# Raincenter_RS232_Converter.net
KiCad netlist of a schematic drawn in EAGLE
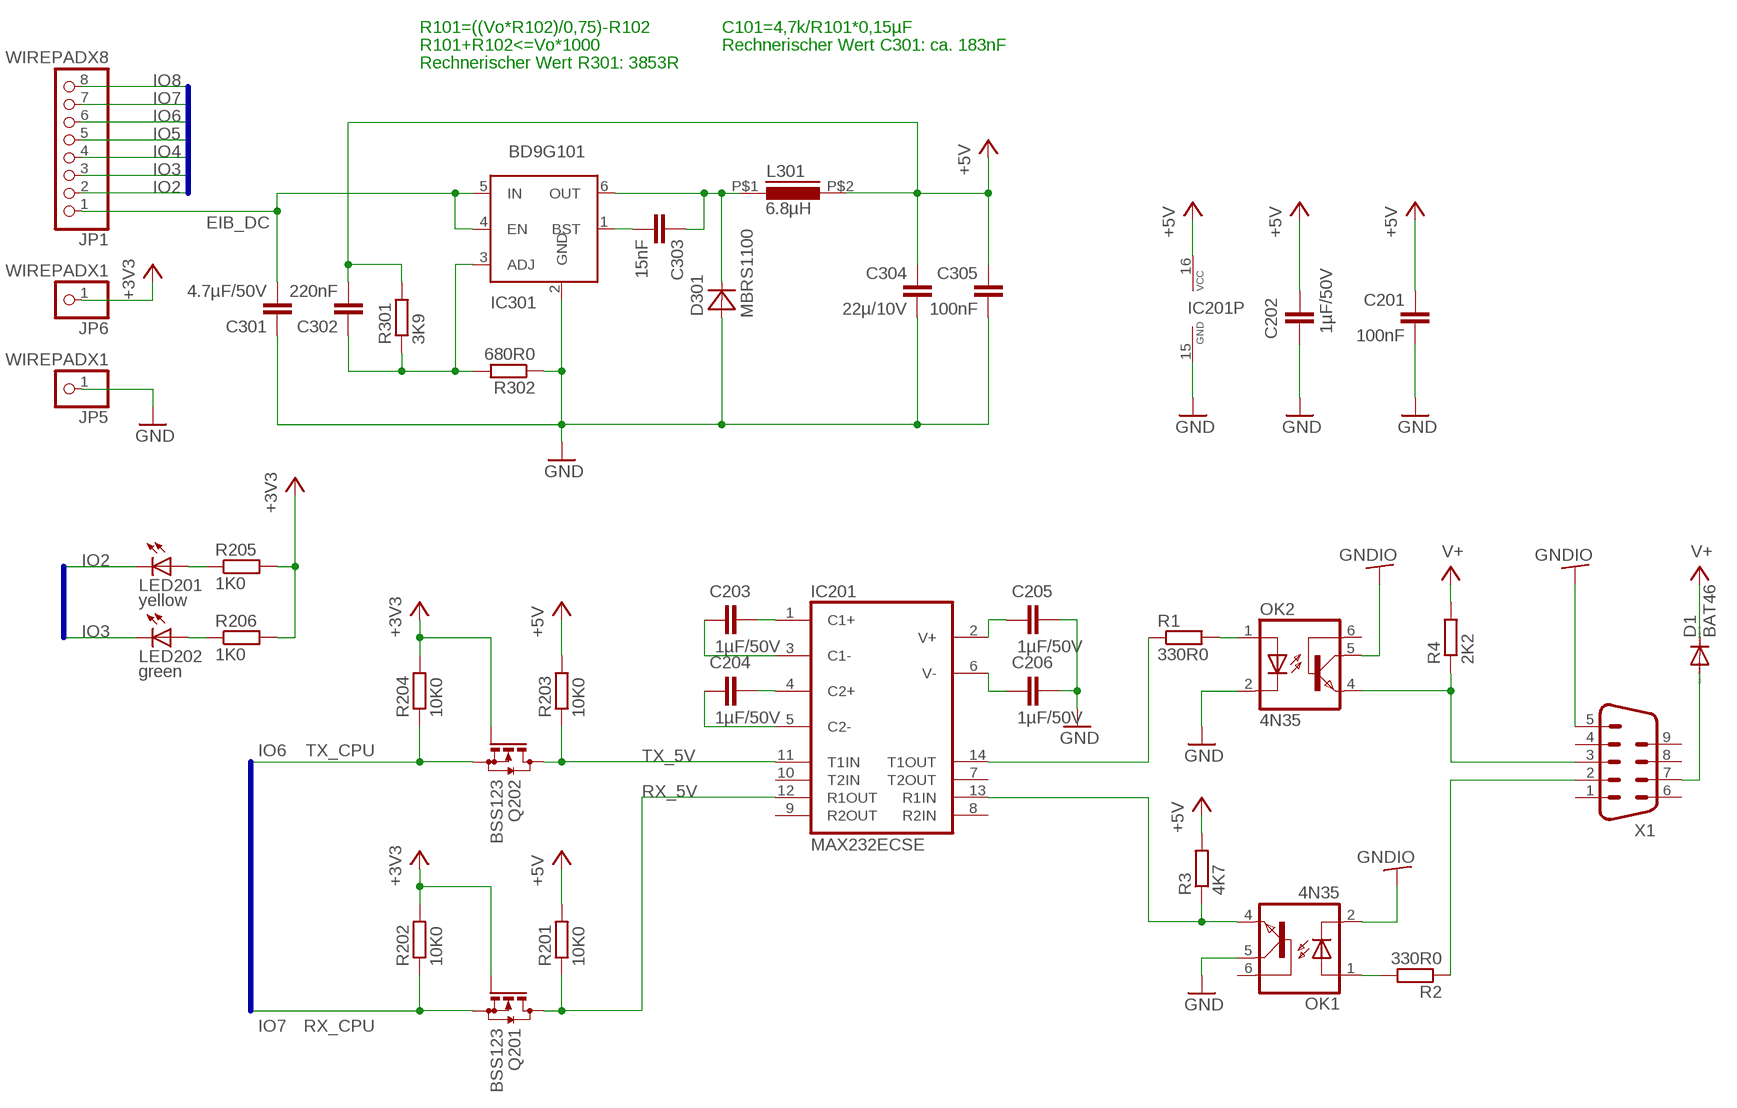
[diagram p0: schematic, sheet 1]

(export (version "E")
  (design (tool "Eeschema 10.0.6"))
  (components
    (comp (ref "C201")
      (value "100nF")
      (footprint "eagle-import:C1206")
      (libsource (lib "eagle-import") (part "C-EUC1206"))
    )
    (comp (ref "C202")
      (value "1µF/50V")
      (footprint "eagle-import:C1206")
      (libsource (lib "eagle-import") (part "C-EUC1206"))
    )
    (comp (ref "C203")
      (value "1µF/50V")
      (footprint "eagle-import:C1206")
      (libsource (lib "eagle-import") (part "C-EUC1206"))
    )
    (comp (ref "C204")
      (value "1µF/50V")
      (footprint "eagle-import:C1206")
      (libsource (lib "eagle-import") (part "C-EUC1206"))
    )
    (comp (ref "C205")
      (value "1µF/50V")
      (footprint "eagle-import:C1206")
      (libsource (lib "eagle-import") (part "C-EUC1206"))
    )
    (comp (ref "C206")
      (value "1µF/50V")
      (footprint "eagle-import:C1206")
      (libsource (lib "eagle-import") (part "C-EUC1206"))
    )
    (comp (ref "C301")
      (value "4.7µF/50V")
      (footprint "eagle-import:C1206")
      (libsource (lib "eagle-import") (part "C-EUC1206"))
    )
    (comp (ref "C302")
      (value "220nF")
      (footprint "eagle-import:C1206")
      (libsource (lib "eagle-import") (part "C-EUC1206"))
    )
    (comp (ref "C303")
      (value "15nF")
      (footprint "eagle-import:C1206")
      (libsource (lib "eagle-import") (part "C-EUC1206"))
    )
    (comp (ref "C304")
      (value "22µ/10V")
      (footprint "eagle-import:C1206")
      (libsource (lib "eagle-import") (part "C-EUC1206"))
    )
    (comp (ref "C305")
      (value "100nF")
      (footprint "eagle-import:C1206")
      (libsource (lib "eagle-import") (part "C-EUC1206"))
    )
    (comp (ref "D1")
      (value "BAT46")
      (footprint "eagle-import:DO35-7")
      (libsource (lib "eagle-import") (part "1N4148DO35-7"))
    )
    (comp (ref "D301")
      (value "MBRS1100")
      (footprint "eagle-import:SMA")
      (libsource (lib "eagle-import") (part "MBRA340T3"))
    )
    (comp (ref "IC201")
      (value "MAX232ECSE")
      (footprint "eagle-import:SO16")
      (fields (field (name "MPN") "MAX3232CSE") (field (name "REICHELT") "MAX 232 ECSE"))
      (libsource (lib "eagle-import") (part "MAX3232SEC"))
    )
    (comp (ref "IC301")
      (value "BD9G101")
      (footprint "eagle-import:SOT23-6")
      (libsource (lib "eagle-import") (part "BD9G101GBD9G101G-SOT23-6"))
    )
    (comp (ref "JP1")
      (value "WIREPADX8")
      (footprint "eagle-import:SMD1,27X2,54X8")
      (libsource (lib "eagle-import") (part "WIREPADX8"))
    )
    (comp (ref "JP5")
      (value "WIREPADX1")
      (footprint "eagle-import:SMD1,27X2,54")
      (libsource (lib "eagle-import") (part "WIREPADX1"))
    )
    (comp (ref "JP6")
      (value "WIREPADX1")
      (footprint "eagle-import:SMD1,27X2,54")
      (libsource (lib "eagle-import") (part "WIREPADX1"))
    )
    (comp (ref "L301")
      (value "6.8µH")
      (footprint "eagle-import:PIS2812")
      (libsource (lib "eagle-import") (part "IND_FASTRON_1616FPS"))
    )
    (comp (ref "LED201")
      (value "yellow")
      (footprint "eagle-import:CHIPLED_1206")
      (libsource (lib "eagle-import") (part "LEDCHIPLED_1206"))
    )
    (comp (ref "LED202")
      (value "green")
      (footprint "eagle-import:CHIPLED_1206")
      (libsource (lib "eagle-import") (part "LEDCHIPLED_1206"))
    )
    (comp (ref "OK1")
      (value "4N35")
      (footprint "eagle-import:DIL06")
      (fields (field (name "MF") "FAIRCHILD SEMICONDUCTOR"))
      (libsource (lib "eagle-import") (part "4N35"))
    )
    (comp (ref "OK2")
      (value "4N35")
      (footprint "eagle-import:DIL06")
      (fields (field (name "MF") "FAIRCHILD SEMICONDUCTOR"))
      (libsource (lib "eagle-import") (part "4N35"))
    )
    (comp (ref "Q201")
      (value "BSS123")
      (footprint "eagle-import:SOT23")
      (libsource (lib "eagle-import") (part "BSS123"))
    )
    (comp (ref "Q202")
      (value "BSS123")
      (footprint "eagle-import:SOT23")
      (libsource (lib "eagle-import") (part "BSS123"))
    )
    (comp (ref "R1")
      (value "330R0")
      (footprint "eagle-import:R1206")
      (libsource (lib "eagle-import") (part "R-EU_R1206"))
    )
    (comp (ref "R2")
      (value "330R0")
      (footprint "eagle-import:R1206")
      (libsource (lib "eagle-import") (part "R-EU_R1206"))
    )
    (comp (ref "R3")
      (value "4K7")
      (footprint "eagle-import:R1206")
      (libsource (lib "eagle-import") (part "R-EU_R1206"))
    )
    (comp (ref "R4")
      (value "2K2")
      (footprint "eagle-import:R1206")
      (libsource (lib "eagle-import") (part "R-EU_R1206"))
    )
    (comp (ref "R201")
      (value "10K0")
      (footprint "eagle-import:R1206")
      (libsource (lib "eagle-import") (part "R-EU_R1206"))
    )
    (comp (ref "R202")
      (value "10K0")
      (footprint "eagle-import:R1206")
      (libsource (lib "eagle-import") (part "R-EU_R1206"))
    )
    (comp (ref "R203")
      (value "10K0")
      (footprint "eagle-import:R1206")
      (libsource (lib "eagle-import") (part "R-EU_R1206"))
    )
    (comp (ref "R204")
      (value "10K0")
      (footprint "eagle-import:R1206")
      (libsource (lib "eagle-import") (part "R-EU_R1206"))
    )
    (comp (ref "R205")
      (value "1K0")
      (footprint "eagle-import:R1206")
      (libsource (lib "eagle-import") (part "R-EU_R1206"))
    )
    (comp (ref "R206")
      (value "1K0")
      (footprint "eagle-import:R1206")
      (libsource (lib "eagle-import") (part "R-EU_R1206"))
    )
    (comp (ref "R301")
      (value "3K9")
      (footprint "eagle-import:R1206")
      (libsource (lib "eagle-import") (part "R-EU_R1206"))
    )
    (comp (ref "R302")
      (value "680R0")
      (footprint "eagle-import:R1206")
      (libsource (lib "eagle-import") (part "R-EU_R1206"))
    )
    (comp (ref "X1")
      (value "M09HP")
      (footprint "eagle-import:M09HP")
      (libsource (lib "eagle-import") (part "M09HP"))
    )
  )
  (nets
    (net (code "1") (name "+3V3") (class "Default")
      (node (ref "JP6") (pin "1") (pinfunction "1_1") (pintype "passive"))
      (node (ref "Q201") (pin "1") (pinfunction "G_1") (pintype "passive"))
      (node (ref "Q202") (pin "1") (pinfunction "G_1") (pintype "passive"))
      (node (ref "R202") (pin "2") (pinfunction "2_2") (pintype "passive"))
      (node (ref "R204") (pin "2") (pinfunction "2_2") (pintype "passive"))
      (node (ref "R205") (pin "2") (pinfunction "2_2") (pintype "passive"))
      (node (ref "R206") (pin "2") (pinfunction "2_2") (pintype "passive"))
    )
    (net (code "2") (name "+5V") (class "Default")
      (node (ref "C201") (pin "1") (pinfunction "1_1") (pintype "passive"))
      (node (ref "C202") (pin "1") (pinfunction "1_1") (pintype "passive"))
      (node (ref "C302") (pin "2") (pinfunction "2_2") (pintype "passive"))
      (node (ref "C304") (pin "1") (pinfunction "1_1") (pintype "passive"))
      (node (ref "C305") (pin "1") (pinfunction "1_1") (pintype "passive"))
      (node (ref "IC201") (pin "16") (pinfunction "VCC_16") (pintype "power_in"))
      (node (ref "L301") (pin "P$2") (pinfunction "2_P$2") (pintype "passive"))
      (node (ref "R201") (pin "2") (pinfunction "2_2") (pintype "passive"))
      (node (ref "R203") (pin "2") (pinfunction "2_2") (pintype "passive"))
      (node (ref "R3") (pin "2") (pinfunction "2_2") (pintype "passive"))
      (node (ref "R301") (pin "2") (pinfunction "2_2") (pintype "passive"))
    )
    (net (code "3") (name "/EIB_DC") (class "Default")
      (node (ref "C301") (pin "2") (pinfunction "2_2") (pintype "passive"))
      (node (ref "IC301") (pin "4") (pinfunction "EN_4") (pintype "input"))
      (node (ref "IC301") (pin "5") (pinfunction "IN_5") (pintype "input"))
      (node (ref "JP1") (pin "1") (pinfunction "1_1") (pintype "passive"))
    )
    (net (code "4") (name "/IO2") (class "Default")
      (node (ref "JP1") (pin "2") (pinfunction "2_2") (pintype "passive"))
      (node (ref "LED201") (pin "C") (pinfunction "C_C") (pintype "passive"))
    )
    (net (code "5") (name "/IO3") (class "Default")
      (node (ref "JP1") (pin "3") (pinfunction "3_3") (pintype "passive"))
      (node (ref "LED202") (pin "C") (pinfunction "C_C") (pintype "passive"))
    )
    (net (code "6") (name "/IO4") (class "Default")
      (node (ref "JP1") (pin "4") (pinfunction "4_4") (pintype "passive"))
    )
    (net (code "7") (name "/IO5") (class "Default")
      (node (ref "JP1") (pin "5") (pinfunction "5_5") (pintype "passive"))
    )
    (net (code "8") (name "/IO6") (class "Default")
      (node (ref "JP1") (pin "6") (pinfunction "6_6") (pintype "passive"))
      (node (ref "Q202") (pin "2") (pinfunction "S_2") (pintype "passive"))
      (node (ref "R204") (pin "1") (pinfunction "1_1") (pintype "passive"))
    )
    (net (code "9") (name "/IO7") (class "Default")
      (node (ref "JP1") (pin "7") (pinfunction "7_7") (pintype "passive"))
      (node (ref "Q201") (pin "2") (pinfunction "S_2") (pintype "passive"))
      (node (ref "R202") (pin "1") (pinfunction "1_1") (pintype "passive"))
    )
    (net (code "10") (name "/IO8") (class "Default")
      (node (ref "JP1") (pin "8") (pinfunction "8_8") (pintype "passive"))
    )
    (net (code "11") (name "/RX_5V") (class "Default")
      (node (ref "IC201") (pin "12") (pinfunction "R1OUT_12") (pintype "output"))
      (node (ref "Q201") (pin "3") (pinfunction "D_3") (pintype "passive"))
      (node (ref "R201") (pin "1") (pinfunction "1_1") (pintype "passive"))
    )
    (net (code "12") (name "/TX_5V") (class "Default")
      (node (ref "IC201") (pin "11") (pinfunction "T1IN_11") (pintype "input"))
      (node (ref "Q202") (pin "3") (pinfunction "D_3") (pintype "passive"))
      (node (ref "R203") (pin "1") (pinfunction "1_1") (pintype "passive"))
    )
    (net (code "13") (name "GND") (class "Default")
      (node (ref "C201") (pin "2") (pinfunction "2_2") (pintype "passive"))
      (node (ref "C202") (pin "2") (pinfunction "2_2") (pintype "passive"))
      (node (ref "C205") (pin "1") (pinfunction "1_1") (pintype "passive"))
      (node (ref "C206") (pin "1") (pinfunction "1_1") (pintype "passive"))
      (node (ref "C301") (pin "1") (pinfunction "1_1") (pintype "passive"))
      (node (ref "C304") (pin "2") (pinfunction "2_2") (pintype "passive"))
      (node (ref "C305") (pin "2") (pinfunction "2_2") (pintype "passive"))
      (node (ref "D301") (pin "A") (pinfunction "A_A") (pintype "passive"))
      (node (ref "IC201") (pin "15") (pinfunction "GND_15") (pintype "power_in"))
      (node (ref "IC301") (pin "2") (pinfunction "GND_2") (pintype "power_in"))
      (node (ref "JP5") (pin "1") (pinfunction "1_1") (pintype "passive"))
      (node (ref "OK1") (pin "5") (pinfunction "COL_5") (pintype "passive"))
      (node (ref "OK2") (pin "2") (pinfunction "C_2") (pintype "passive"))
      (node (ref "R302") (pin "1") (pinfunction "1_1") (pintype "passive"))
    )
    (net (code "14") (name "GNDIO") (class "Default")
      (node (ref "OK1") (pin "2") (pinfunction "C_2") (pintype "passive"))
      (node (ref "OK2") (pin "5") (pinfunction "COL_5") (pintype "passive"))
      (node (ref "X1") (pin "5") (pinfunction "5_5") (pintype "passive"))
    )
    (net (code "15") (name "Net-(D1-PadA)") (class "Default")
      (node (ref "D1") (pin "A") (pinfunction "A_A") (pintype "passive"))
      (node (ref "X1") (pin "7") (pinfunction "7_7") (pintype "passive"))
    )
    (net (code "16") (name "Net-(IC201A-C1+)") (class "Default")
      (node (ref "C203") (pin "1") (pinfunction "1_1") (pintype "passive"))
      (node (ref "IC201") (pin "1") (pinfunction "C1+_1") (pintype "bidirectional"))
    )
    (net (code "17") (name "Net-(IC201A-C1-)") (class "Default")
      (node (ref "C203") (pin "2") (pinfunction "2_2") (pintype "passive"))
      (node (ref "IC201") (pin "3") (pinfunction "C1-_3") (pintype "bidirectional"))
    )
    (net (code "18") (name "Net-(IC201A-C2+)") (class "Default")
      (node (ref "C204") (pin "1") (pinfunction "1_1") (pintype "passive"))
      (node (ref "IC201") (pin "4") (pinfunction "C2+_4") (pintype "bidirectional"))
    )
    (net (code "19") (name "Net-(IC201A-C2-)") (class "Default")
      (node (ref "C204") (pin "2") (pinfunction "2_2") (pintype "passive"))
      (node (ref "IC201") (pin "5") (pinfunction "C2-_5") (pintype "bidirectional"))
    )
    (net (code "20") (name "Net-(IC201A-R1IN)") (class "Default")
      (node (ref "IC201") (pin "13") (pinfunction "R1IN_13") (pintype "input"))
      (node (ref "OK1") (pin "4") (pinfunction "EMI_4") (pintype "passive"))
      (node (ref "R3") (pin "1") (pinfunction "1_1") (pintype "passive"))
    )
    (net (code "21") (name "Net-(IC201A-T1OUT)") (class "Default")
      (node (ref "IC201") (pin "14") (pinfunction "T1OUT_14") (pintype "output"))
      (node (ref "R1") (pin "1") (pinfunction "1_1") (pintype "passive"))
    )
    (net (code "22") (name "Net-(IC201A-V+)") (class "Default")
      (node (ref "C205") (pin "2") (pinfunction "2_2") (pintype "passive"))
      (node (ref "IC201") (pin "2") (pinfunction "V+_2") (pintype "bidirectional"))
    )
    (net (code "23") (name "Net-(IC201A-V-)") (class "Default")
      (node (ref "C206") (pin "2") (pinfunction "2_2") (pintype "passive"))
      (node (ref "IC201") (pin "6") (pinfunction "V-_6") (pintype "bidirectional"))
    )
    (net (code "24") (name "Net-(IC301-ADJ)") (class "Default")
      (node (ref "C302") (pin "1") (pinfunction "1_1") (pintype "passive"))
      (node (ref "IC301") (pin "3") (pinfunction "ADJ_3") (pintype "passive"))
      (node (ref "R301") (pin "1") (pinfunction "1_1") (pintype "passive"))
      (node (ref "R302") (pin "2") (pinfunction "2_2") (pintype "passive"))
    )
    (net (code "25") (name "Net-(IC301-BST)") (class "Default")
      (node (ref "C303") (pin "2") (pinfunction "2_2") (pintype "passive"))
      (node (ref "IC301") (pin "1") (pinfunction "BST_1") (pintype "output"))
    )
    (net (code "26") (name "Net-(IC301-OUT)") (class "Default")
      (node (ref "C303") (pin "1") (pinfunction "1_1") (pintype "passive"))
      (node (ref "D301") (pin "C") (pinfunction "C_C") (pintype "passive"))
      (node (ref "IC301") (pin "6") (pinfunction "OUT_6") (pintype "output"))
      (node (ref "L301") (pin "P$1") (pinfunction "1_P$1") (pintype "passive"))
    )
    (net (code "27") (name "Net-(LED201-PadA)") (class "Default")
      (node (ref "LED201") (pin "A") (pinfunction "A_A") (pintype "passive"))
      (node (ref "R205") (pin "1") (pinfunction "1_1") (pintype "passive"))
    )
    (net (code "28") (name "Net-(LED202-PadA)") (class "Default")
      (node (ref "LED202") (pin "A") (pinfunction "A_A") (pintype "passive"))
      (node (ref "R206") (pin "1") (pinfunction "1_1") (pintype "passive"))
    )
    (net (code "29") (name "Net-(OK1-A)") (class "Default")
      (node (ref "OK1") (pin "1") (pinfunction "A_1") (pintype "passive"))
      (node (ref "R2") (pin "2") (pinfunction "2_2") (pintype "passive"))
    )
    (net (code "30") (name "Net-(OK2-A)") (class "Default")
      (node (ref "OK2") (pin "1") (pinfunction "A_1") (pintype "passive"))
      (node (ref "R1") (pin "2") (pinfunction "2_2") (pintype "passive"))
    )
    (net (code "31") (name "Net-(OK2-EMI)") (class "Default")
      (node (ref "OK2") (pin "4") (pinfunction "EMI_4") (pintype "passive"))
      (node (ref "R4") (pin "1") (pinfunction "1_1") (pintype "passive"))
      (node (ref "X1") (pin "3") (pinfunction "3_3") (pintype "passive"))
    )
    (net (code "32") (name "Net-(R2-Pad1)") (class "Default")
      (node (ref "R2") (pin "1") (pinfunction "1_1") (pintype "passive"))
      (node (ref "X1") (pin "2") (pinfunction "2_2") (pintype "passive"))
    )
    (net (code "33") (name "V+") (class "Default")
      (node (ref "D1") (pin "C") (pinfunction "C_C") (pintype "passive"))
      (node (ref "R4") (pin "2") (pinfunction "2_2") (pintype "passive"))
    )
    (net (code "34") (name "unconnected-(IC201A-R2IN-Pad8)") (class "Default")
      (node (ref "IC201") (pin "8") (pinfunction "R2IN_8") (pintype "input"))
    )
    (net (code "35") (name "unconnected-(IC201A-R2OUT-Pad9)") (class "Default")
      (node (ref "IC201") (pin "9") (pinfunction "R2OUT_9") (pintype "output"))
    )
    (net (code "36") (name "unconnected-(IC201A-T2IN-Pad10)") (class "Default")
      (node (ref "IC201") (pin "10") (pinfunction "T2IN_10") (pintype "input"))
    )
    (net (code "37") (name "unconnected-(IC201A-T2OUT-Pad7)") (class "Default")
      (node (ref "IC201") (pin "7") (pinfunction "T2OUT_7") (pintype "output"))
    )
    (net (code "38") (name "unconnected-(OK1-BAS-Pad6)") (class "Default")
      (node (ref "OK1") (pin "6") (pinfunction "BAS_6") (pintype "passive"))
    )
    (net (code "39") (name "unconnected-(OK2-BAS-Pad6)") (class "Default")
      (node (ref "OK2") (pin "6") (pinfunction "BAS_6") (pintype "passive"))
    )
    (net (code "40") (name "unconnected-(X1-Pad1)") (class "Default")
      (node (ref "X1") (pin "1") (pinfunction "1_1") (pintype "passive"))
    )
    (net (code "41") (name "unconnected-(X1-Pad4)") (class "Default")
      (node (ref "X1") (pin "4") (pinfunction "4_4") (pintype "passive"))
    )
    (net (code "42") (name "unconnected-(X1-Pad6)") (class "Default")
      (node (ref "X1") (pin "6") (pinfunction "6_6") (pintype "passive"))
    )
    (net (code "43") (name "unconnected-(X1-Pad8)") (class "Default")
      (node (ref "X1") (pin "8") (pinfunction "8_8") (pintype "passive"))
    )
    (net (code "44") (name "unconnected-(X1-Pad9)") (class "Default")
      (node (ref "X1") (pin "9") (pinfunction "9_9") (pintype "passive"))
    )
  )
)
